# PhantomPowerSupply_Schematic.net
KiCad netlist of a schematic drawn in Altium Designer
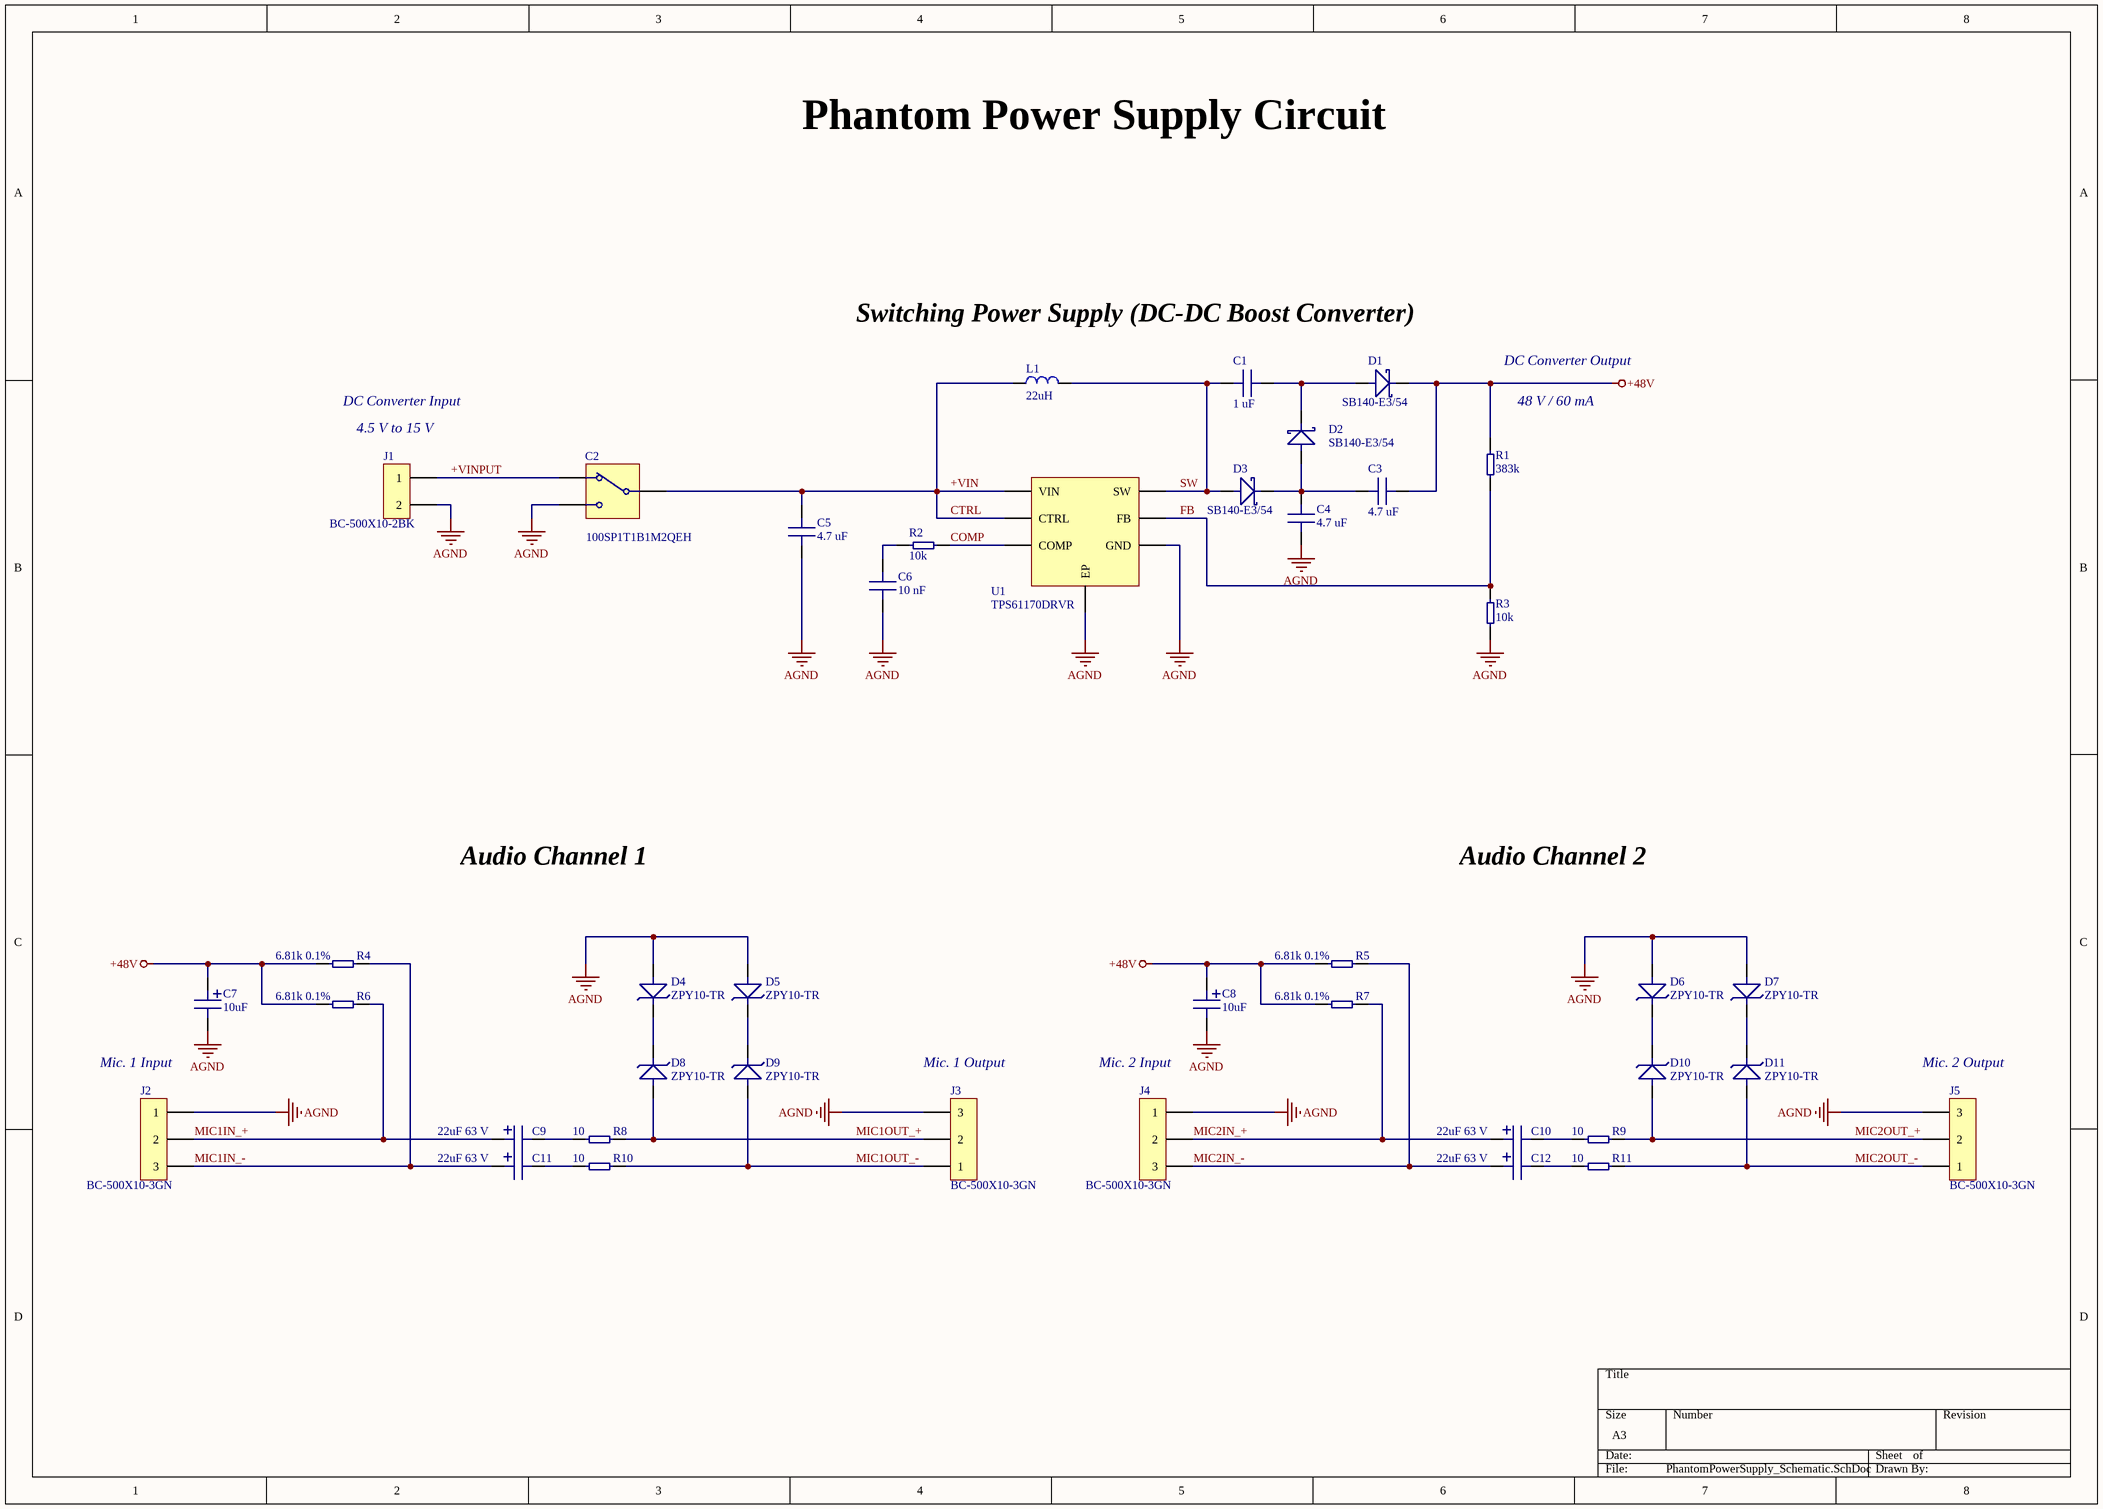
[diagram p0: PhantomPowerSupply_Schematic.SchDoc]

(export (version "E")
  (design (tool "Eeschema 10.0.6"))
  (components
    (comp (ref "C1")
      (value "1 uF")
      (footprint "CRADIAL-CERAMIC-BROWN")
      (description "Multilayer Ceramic Capacitors MLCC - Leaded 1uF 50volts 10% X7R 5mm LS")
      (fields
        (field (name "MANUFACTURER") "Vishay / BC Components")
        (field (name "MANUFACTURER PART NUMBER") "K105K20X7RF5TH5")
      )
      (libsource (lib "PhantomPowerSupply_SchematicLibrary") (part "K105K20X7RF5TH5"))
    )
    (comp (ref "C2")
      (value "100SP1T1B1M2QEH")
      (footprint "SPDT-M2")
      (description "Toggle Switches SPDT ON-ON PC MNT")
      (fields (field (name "MANUFACTURER") "E-Switch"))
      (libsource (lib "PhantomPowerSupply_SchematicLibrary") (part "100SP1T1B1M2QEH"))
    )
    (comp (ref "C3")
      (value "4.7 uF")
      (footprint "CRADIAL-CERAMIC")
      (description "Multilayer Ceramic Capacitors MLCC - Leaded 4.7uF 50volts X7R +/-10%")
      (fields (field (name "MANUFACTURER") "TDK") (field (name "MANUFACTURER PART NUMBER") "FK11X7R1H475K"))
      (libsource (lib "PhantomPowerSupply_SchematicLibrary") (part "FK11X7R1H475K"))
    )
    (comp (ref "C4")
      (value "4.7 uF")
      (footprint "CRADIAL-CERAMIC")
      (description "Multilayer Ceramic Capacitors MLCC - Leaded 4.7uF 50volts X7R +/-10%")
      (fields (field (name "MANUFACTURER") "TDK") (field (name "MANUFACTURER PART NUMBER") "FK11X7R1H475K"))
      (libsource (lib "PhantomPowerSupply_SchematicLibrary") (part "FK11X7R1H475K"))
    )
    (comp (ref "C5")
      (value "4.7 uF")
      (footprint "CRADIAL-CERAMIC")
      (description "Multilayer Ceramic Capacitors MLCC - Leaded 4.7uF 50volts X7R +/-10%")
      (fields (field (name "MANUFACTURER") "TDK") (field (name "MANUFACTURER PART NUMBER") "FK11X7R1H475K"))
      (libsource (lib "PhantomPowerSupply_SchematicLibrary") (part "FK11X7R1H475K"))
    )
    (comp (ref "C6")
      (value "10 nF")
      (footprint "CRADIAL-CERAMIC-BROWN")
      (description "Multilayer Ceramic Capacitors MLCC - Leaded .01uF 50volts 10% 5.0mm X7R")
      (fields
        (field (name "MANUFACTURER") "Vishay / BC Components")
        (field (name "MANUFACTURER PART NUMBER") "K103K15X7RF5UH5")
      )
      (libsource (lib "PhantomPowerSupply_SchematicLibrary") (part "K103K15X7RF5UH5"))
    )
    (comp (ref "C7")
      (value "10uF")
      (footprint "C-ELECTROLYTIC-RADIAL")
      (description "Aluminium Electrolytic Capacitors - Leaded 50V 10uF 20% 5x11mm")
      (fields
        (field (name "MANUFACTURER") "Lelon")
        (field (name "MANUFACTURER PART NUMBER") "REA100M1HBK-0511P")
      )
      (libsource (lib "PhantomPowerSupply_SchematicLibrary") (part "REA100M1HBK-0511P"))
    )
    (comp (ref "C8")
      (value "10uF")
      (footprint "C-ELECTROLYTIC-RADIAL")
      (description "Aluminium Electrolytic Capacitors - Leaded 50V 10uF 20% 5x11mm")
      (fields
        (field (name "MANUFACTURER") "Lelon")
        (field (name "MANUFACTURER PART NUMBER") "REA100M1HBK-0511P")
      )
      (libsource (lib "PhantomPowerSupply_SchematicLibrary") (part "REA100M1HBK-0511P"))
    )
    (comp (ref "C9")
      (value "22uF 63 V")
      (footprint "C-ELECTROLYTIC-RADIAL")
      (description "Aluminium Electrolytic Capacitors - Leaded 63V 22uF 20% 6.3x11 mm")
      (fields
        (field (name "MANUFACTURER") "Lelon")
        (field (name "MANUFACTURER PART NUMBER") "REA220M1JBK-0611P")
      )
      (libsource (lib "PhantomPowerSupply_SchematicLibrary") (part "REA220M1JBK-0611P"))
    )
    (comp (ref "C10")
      (value "22uF 63 V")
      (footprint "C-ELECTROLYTIC-RADIAL")
      (description "Aluminium Electrolytic Capacitors - Leaded 63V 22uF 20% 6.3x11 mm")
      (fields
        (field (name "MANUFACTURER") "Lelon")
        (field (name "MANUFACTURER PART NUMBER") "REA220M1JBK-0611P")
      )
      (libsource (lib "PhantomPowerSupply_SchematicLibrary") (part "REA220M1JBK-0611P"))
    )
    (comp (ref "C11")
      (value "22uF 63 V")
      (footprint "C-ELECTROLYTIC-RADIAL")
      (description "Aluminium Electrolytic Capacitors - Leaded 63V 22uF 20% 6.3x11 mm")
      (fields
        (field (name "MANUFACTURER") "Lelon")
        (field (name "MANUFACTURER PART NUMBER") "REA220M1JBK-0611P")
      )
      (libsource (lib "PhantomPowerSupply_SchematicLibrary") (part "REA220M1JBK-0611P"))
    )
    (comp (ref "C12")
      (value "22uF 63 V")
      (footprint "C-ELECTROLYTIC-RADIAL")
      (description "Aluminium Electrolytic Capacitors - Leaded 63V 22uF 20% 6.3x11 mm")
      (fields
        (field (name "MANUFACTURER") "Lelon")
        (field (name "MANUFACTURER PART NUMBER") "REA220M1JBK-0611P")
      )
      (libsource (lib "PhantomPowerSupply_SchematicLibrary") (part "REA220M1JBK-0611P"))
    )
    (comp (ref "D1")
      (value "SB140-E3/54")
      (footprint "D-SCHOTTKY-AXIAL")
      (description "Schottky Diodes & Rectifiers 40 Volt 1.0 Amp 50 Amp IFSM")
      (fields (field (name "MANUFACTURER") "Vishay Semiconductors"))
      (libsource (lib "PhantomPowerSupply_SchematicLibrary") (part "SB140-E3/54"))
    )
    (comp (ref "D2")
      (value "SB140-E3/54")
      (footprint "D-SCHOTTKY-AXIAL")
      (description "Schottky Diodes & Rectifiers 40 Volt 1.0 Amp 50 Amp IFSM")
      (fields (field (name "MANUFACTURER") "Vishay Semiconductors"))
      (libsource (lib "PhantomPowerSupply_SchematicLibrary") (part "SB140-E3/54"))
    )
    (comp (ref "D3")
      (value "SB140-E3/54")
      (footprint "D-SCHOTTKY-AXIAL")
      (description "Schottky Diodes & Rectifiers 40 Volt 1.0 Amp 50 Amp IFSM")
      (fields (field (name "MANUFACTURER") "Vishay Semiconductors"))
      (libsource (lib "PhantomPowerSupply_SchematicLibrary") (part "SB140-E3/54"))
    )
    (comp (ref "D4")
      (value "ZPY10-TR")
      (footprint "D-ZENER-AXIAL")
      (description "Zener Diodes 10 Volt 1.3 Watt 5%")
      (fields (field (name "MANUFACTURER") "Vishay Semiconductors"))
      (libsource (lib "PhantomPowerSupply_SchematicLibrary") (part "ZPY10-TR"))
    )
    (comp (ref "D5")
      (value "ZPY10-TR")
      (footprint "D-ZENER-AXIAL")
      (description "Zener Diodes 10 Volt 1.3 Watt 5%")
      (fields (field (name "MANUFACTURER") "Vishay Semiconductors"))
      (libsource (lib "PhantomPowerSupply_SchematicLibrary") (part "ZPY10-TR"))
    )
    (comp (ref "D6")
      (value "ZPY10-TR")
      (footprint "D-ZENER-AXIAL")
      (description "Zener Diodes 10 Volt 1.3 Watt 5%")
      (fields (field (name "MANUFACTURER") "Vishay Semiconductors"))
      (libsource (lib "PhantomPowerSupply_SchematicLibrary") (part "ZPY10-TR"))
    )
    (comp (ref "D7")
      (value "ZPY10-TR")
      (footprint "D-ZENER-AXIAL")
      (description "Zener Diodes 10 Volt 1.3 Watt 5%")
      (fields (field (name "MANUFACTURER") "Vishay Semiconductors"))
      (libsource (lib "PhantomPowerSupply_SchematicLibrary") (part "ZPY10-TR"))
    )
    (comp (ref "D8")
      (value "ZPY10-TR")
      (footprint "D-ZENER-AXIAL")
      (description "Zener Diodes 10 Volt 1.3 Watt 5%")
      (fields (field (name "MANUFACTURER") "Vishay Semiconductors"))
      (libsource (lib "PhantomPowerSupply_SchematicLibrary") (part "ZPY10-TR"))
    )
    (comp (ref "D9")
      (value "ZPY10-TR")
      (footprint "D-ZENER-AXIAL")
      (description "Zener Diodes 10 Volt 1.3 Watt 5%")
      (fields (field (name "MANUFACTURER") "Vishay Semiconductors"))
      (libsource (lib "PhantomPowerSupply_SchematicLibrary") (part "ZPY10-TR"))
    )
    (comp (ref "D10")
      (value "ZPY10-TR")
      (footprint "D-ZENER-AXIAL")
      (description "Zener Diodes 10 Volt 1.3 Watt 5%")
      (fields (field (name "MANUFACTURER") "Vishay Semiconductors"))
      (libsource (lib "PhantomPowerSupply_SchematicLibrary") (part "ZPY10-TR"))
    )
    (comp (ref "D11")
      (value "ZPY10-TR")
      (footprint "D-ZENER-AXIAL")
      (description "Zener Diodes 10 Volt 1.3 Watt 5%")
      (fields (field (name "MANUFACTURER") "Vishay Semiconductors"))
      (libsource (lib "PhantomPowerSupply_SchematicLibrary") (part "ZPY10-TR"))
    )
    (comp (ref "J1")
      (value "BC-500X10-2BK")
      (footprint "SCREW-CON-2POS")
      (description "Fixed Terminal Blocks BC-500X10- 2 BK")
      (fields
        (field (name "MANUFACTURER") "Phoenix Contact")
        (field (name "MANUFACTURER PART NUMBER") "5441537")
      )
      (libsource (lib "PhantomPowerSupply_SchematicLibrary") (part "5441537"))
    )
    (comp (ref "J2")
      (value "BC-500X10-3GN")
      (footprint "SCREW-CON-3POS")
      (description "Fixed Terminal Blocks BC-500X10- 3 GN 5.00 MM PITCH")
      (fields
        (field (name "MANUFACTURER") "Phoenix Contact")
        (field (name "MANUFACTURER PART NUMBER") "5442183")
      )
      (libsource (lib "") (part "5442183_1"))
    )
    (comp (ref "J3")
      (value "BC-500X10-3GN")
      (footprint "SCREW-CON-3POS")
      (description "Fixed Terminal Blocks BC-500X10- 3 GN 5.00 MM PITCH")
      (fields
        (field (name "MANUFACTURER") "Phoenix Contact")
        (field (name "MANUFACTURER PART NUMBER") "5442183")
      )
      (libsource (lib "PhantomPowerSupply_SchematicLibrary") (part "5442183"))
    )
    (comp (ref "J4")
      (value "BC-500X10-3GN")
      (footprint "SCREW-CON-3POS")
      (description "Fixed Terminal Blocks BC-500X10- 3 GN 5.00 MM PITCH")
      (fields
        (field (name "MANUFACTURER") "Phoenix Contact")
        (field (name "MANUFACTURER PART NUMBER") "5442183")
      )
      (libsource (lib "") (part "5442183_1"))
    )
    (comp (ref "J5")
      (value "BC-500X10-3GN")
      (footprint "SCREW-CON-3POS")
      (description "Fixed Terminal Blocks BC-500X10- 3 GN 5.00 MM PITCH")
      (fields
        (field (name "MANUFACTURER") "Phoenix Contact")
        (field (name "MANUFACTURER PART NUMBER") "5442183")
      )
      (libsource (lib "PhantomPowerSupply_SchematicLibrary") (part "5442183"))
    )
    (comp (ref "L1")
      (value "22uH")
      (footprint "L-AXIAL")
      (description "Fixed Inductors 22uH 5%")
      (fields
        (field (name "MANUFACTURER") "J.W. Miller")
        (field (name "MANUFACTURER PART NUMBER") "78F220J-RC")
      )
      (libsource (lib "PhantomPowerSupply_SchematicLibrary") (part "78F220J-RC"))
    )
    (comp (ref "R1")
      (value "383k")
      (footprint "R-AXIAL")
      (description "Metal Film Resistors - Through Hole 1/4 WATT 383K OHM 1%")
      (fields
        (field (name "MANUFACTURER") "KOA Speer")
        (field (name "MANUFACTURER PART NUMBER") "MF1/4DCT26A3833F")
      )
      (libsource (lib "PhantomPowerSupply_SchematicLibrary") (part "MF1/4DCT26A3833F"))
    )
    (comp (ref "R2")
      (value "10k")
      (footprint "R-AXIAL")
      (description "Metal Film Resistors - Through Hole 1/4 WATT 10K OHM 1%")
      (fields
        (field (name "MANUFACTURER") "KOA Speer")
        (field (name "MANUFACTURER PART NUMBER") "MF1/4DCT52A1002F")
      )
      (libsource (lib "PhantomPowerSupply_SchematicLibrary") (part "MF1/4DCT52A1002F"))
    )
    (comp (ref "R3")
      (value "10k")
      (footprint "R-AXIAL")
      (description "Metal Film Resistors - Through Hole 1/4 WATT 10K OHM 1%")
      (fields
        (field (name "MANUFACTURER") "KOA Speer")
        (field (name "MANUFACTURER PART NUMBER") "MF1/4DCT52A1002F")
      )
      (libsource (lib "PhantomPowerSupply_SchematicLibrary") (part "MF1/4DCT52A1002F"))
    )
    (comp (ref "R4")
      (value "6.81k 0.1%")
      (footprint "R-AXIAL")
      (description "Metal Film Resistors - Through Hole 1/10watt 6.81Kohms .1% 25ppm")
      (fields
        (field (name "MANUFACTURER") "Vishay / Dale")
        (field (name "MANUFACTURER PART NUMBER") "RN55E6811BRE6")
      )
      (libsource (lib "PhantomPowerSupply_SchematicLibrary") (part "RN55E6811BRE6"))
    )
    (comp (ref "R5")
      (value "6.81k 0.1%")
      (footprint "R-AXIAL")
      (description "Metal Film Resistors - Through Hole 1/10watt 6.81Kohms .1% 25ppm")
      (fields
        (field (name "MANUFACTURER") "Vishay / Dale")
        (field (name "MANUFACTURER PART NUMBER") "RN55E6811BRE6")
      )
      (libsource (lib "PhantomPowerSupply_SchematicLibrary") (part "RN55E6811BRE6"))
    )
    (comp (ref "R6")
      (value "6.81k 0.1%")
      (footprint "R-AXIAL")
      (description "Metal Film Resistors - Through Hole 1/10watt 6.81Kohms .1% 25ppm")
      (fields
        (field (name "MANUFACTURER") "Vishay / Dale")
        (field (name "MANUFACTURER PART NUMBER") "RN55E6811BRE6")
      )
      (libsource (lib "PhantomPowerSupply_SchematicLibrary") (part "RN55E6811BRE6"))
    )
    (comp (ref "R7")
      (value "6.81k 0.1%")
      (footprint "R-AXIAL")
      (description "Metal Film Resistors - Through Hole 1/10watt 6.81Kohms .1% 25ppm")
      (fields
        (field (name "MANUFACTURER") "Vishay / Dale")
        (field (name "MANUFACTURER PART NUMBER") "RN55E6811BRE6")
      )
      (libsource (lib "PhantomPowerSupply_SchematicLibrary") (part "RN55E6811BRE6"))
    )
    (comp (ref "R8")
      (value "10")
      (footprint "R-AXIAL")
      (description "Metal Film Resistors - Through Hole 10 OHM 1/2W 5%")
      (fields
        (field (name "MANUFACTURER") "Yageo")
        (field (name "MANUFACTURER PART NUMBER") "FRM-50JT-52-10R")
      )
      (libsource (lib "PhantomPowerSupply_SchematicLibrary") (part "FRM-50JT-52-10R"))
    )
    (comp (ref "R9")
      (value "10")
      (footprint "R-AXIAL")
      (description "Metal Film Resistors - Through Hole 10 OHM 1/2W 5%")
      (fields
        (field (name "MANUFACTURER") "Yageo")
        (field (name "MANUFACTURER PART NUMBER") "FRM-50JT-52-10R")
      )
      (libsource (lib "PhantomPowerSupply_SchematicLibrary") (part "FRM-50JT-52-10R"))
    )
    (comp (ref "R10")
      (value "10")
      (footprint "R-AXIAL")
      (description "Metal Film Resistors - Through Hole 10 OHM 1/2W 5%")
      (fields
        (field (name "MANUFACTURER") "Yageo")
        (field (name "MANUFACTURER PART NUMBER") "FRM-50JT-52-10R")
      )
      (libsource (lib "PhantomPowerSupply_SchematicLibrary") (part "FRM-50JT-52-10R"))
    )
    (comp (ref "R11")
      (value "10")
      (footprint "R-AXIAL")
      (description "Metal Film Resistors - Through Hole 10 OHM 1/2W 5%")
      (fields
        (field (name "MANUFACTURER") "Yageo")
        (field (name "MANUFACTURER PART NUMBER") "FRM-50JT-52-10R")
      )
      (libsource (lib "PhantomPowerSupply_SchematicLibrary") (part "FRM-50JT-52-10R"))
    )
    (comp (ref "U1")
      (value "TPS61170DRVR")
      (footprint "S-PWSON-N6")
      (description "Voltage Regulators - Switching Regulators 1.2A Sw Hi Vltg Boost Conv")
      (fields (field (name "MANUFACTURER") "Texas Instruments"))
      (libsource (lib "PhantomPowerSupply_SchematicLibrary") (part "TPS61170DRVR"))
    )
  )
  (nets
    (net (code "1") (name "+48V") (class "Default")
      (node (ref "C3") (pin "2") (pinfunction "2_2") (pintype "passive"))
      (node (ref "C7") (pin "1") (pinfunction "1_1") (pintype "passive"))
      (node (ref "C8") (pin "1") (pinfunction "1_1") (pintype "passive"))
      (node (ref "D1") (pin "2") (pinfunction "2_2") (pintype "passive"))
      (node (ref "R1") (pin "2") (pinfunction "2_2") (pintype "passive"))
      (node (ref "R4") (pin "1") (pinfunction "1_1") (pintype "passive"))
      (node (ref "R5") (pin "1") (pinfunction "1_1") (pintype "passive"))
      (node (ref "R6") (pin "1") (pinfunction "1_1") (pintype "passive"))
      (node (ref "R7") (pin "1") (pinfunction "1_1") (pintype "passive"))
    )
    (net (code "2") (name "/+VIN") (class "Default")
      (node (ref "C2") (pin "2") (pinfunction "2_2") (pintype "passive"))
      (node (ref "C5") (pin "2") (pinfunction "2_2") (pintype "passive"))
      (node (ref "L1") (pin "1") (pinfunction "1_1") (pintype "passive"))
      (node (ref "U1") (pin "5") (pinfunction "CTRL_5") (pintype "passive"))
      (node (ref "U1") (pin "6") (pinfunction "VIN_6") (pintype "passive"))
    )
    (net (code "3") (name "/+VINPUT") (class "Default")
      (node (ref "C2") (pin "1") (pinfunction "1_1") (pintype "passive"))
      (node (ref "J1") (pin "1") (pinfunction "1_1") (pintype "passive"))
    )
    (net (code "4") (name "/COMP") (class "Default")
      (node (ref "R2") (pin "2") (pinfunction "2_2") (pintype "passive"))
      (node (ref "U1") (pin "2") (pinfunction "COMP_2") (pintype "passive"))
    )
    (net (code "5") (name "/FB") (class "Default")
      (node (ref "R1") (pin "1") (pinfunction "1_1") (pintype "passive"))
      (node (ref "R3") (pin "2") (pinfunction "2_2") (pintype "passive"))
      (node (ref "U1") (pin "1") (pinfunction "FB_1") (pintype "passive"))
    )
    (net (code "6") (name "/MIC1IN_+") (class "Default")
      (node (ref "C9") (pin "1") (pinfunction "1_1") (pintype "passive"))
      (node (ref "J2") (pin "2") (pinfunction "2_2") (pintype "passive"))
      (node (ref "R6") (pin "2") (pinfunction "2_2") (pintype "passive"))
    )
    (net (code "7") (name "/MIC1IN_-") (class "Default")
      (node (ref "C11") (pin "1") (pinfunction "1_1") (pintype "passive"))
      (node (ref "J2") (pin "3") (pinfunction "3_3") (pintype "passive"))
      (node (ref "R4") (pin "2") (pinfunction "2_2") (pintype "passive"))
    )
    (net (code "8") (name "/MIC1OUT_+") (class "Default")
      (node (ref "D8") (pin "1") (pinfunction "1_1") (pintype "passive"))
      (node (ref "J3") (pin "2") (pinfunction "2_2") (pintype "passive"))
      (node (ref "R8") (pin "2") (pinfunction "2_2") (pintype "passive"))
    )
    (net (code "9") (name "/MIC1OUT_-") (class "Default")
      (node (ref "D9") (pin "1") (pinfunction "1_1") (pintype "passive"))
      (node (ref "J3") (pin "1") (pinfunction "1_1") (pintype "passive"))
      (node (ref "R10") (pin "2") (pinfunction "2_2") (pintype "passive"))
    )
    (net (code "10") (name "/MIC2IN_+") (class "Default")
      (node (ref "C10") (pin "1") (pinfunction "1_1") (pintype "passive"))
      (node (ref "J4") (pin "2") (pinfunction "2_2") (pintype "passive"))
      (node (ref "R7") (pin "2") (pinfunction "2_2") (pintype "passive"))
    )
    (net (code "11") (name "/MIC2IN_-") (class "Default")
      (node (ref "C12") (pin "1") (pinfunction "1_1") (pintype "passive"))
      (node (ref "J4") (pin "3") (pinfunction "3_3") (pintype "passive"))
      (node (ref "R5") (pin "2") (pinfunction "2_2") (pintype "passive"))
    )
    (net (code "12") (name "/MIC2OUT_+") (class "Default")
      (node (ref "D10") (pin "1") (pinfunction "1_1") (pintype "passive"))
      (node (ref "J5") (pin "2") (pinfunction "2_2") (pintype "passive"))
      (node (ref "R9") (pin "2") (pinfunction "2_2") (pintype "passive"))
    )
    (net (code "13") (name "/MIC2OUT_-") (class "Default")
      (node (ref "D11") (pin "1") (pinfunction "1_1") (pintype "passive"))
      (node (ref "J5") (pin "1") (pinfunction "1_1") (pintype "passive"))
      (node (ref "R11") (pin "2") (pinfunction "2_2") (pintype "passive"))
    )
    (net (code "14") (name "/SW") (class "Default")
      (node (ref "C1") (pin "1") (pinfunction "1_1") (pintype "passive"))
      (node (ref "D3") (pin "1") (pinfunction "1_1") (pintype "passive"))
      (node (ref "L1") (pin "2") (pinfunction "2_2") (pintype "passive"))
      (node (ref "U1") (pin "4") (pinfunction "SW_4") (pintype "passive"))
    )
    (net (code "15") (name "AGND") (class "Default")
      (node (ref "C2") (pin "3") (pinfunction "3_3") (pintype "passive"))
      (node (ref "C4") (pin "1") (pinfunction "1_1") (pintype "passive"))
      (node (ref "C5") (pin "1") (pinfunction "1_1") (pintype "passive"))
      (node (ref "C6") (pin "1") (pinfunction "1_1") (pintype "passive"))
      (node (ref "C7") (pin "2") (pinfunction "2_2") (pintype "passive"))
      (node (ref "C8") (pin "2") (pinfunction "2_2") (pintype "passive"))
      (node (ref "D4") (pin "1") (pinfunction "1_1") (pintype "passive"))
      (node (ref "D5") (pin "1") (pinfunction "1_1") (pintype "passive"))
      (node (ref "D6") (pin "1") (pinfunction "1_1") (pintype "passive"))
      (node (ref "D7") (pin "1") (pinfunction "1_1") (pintype "passive"))
      (node (ref "J1") (pin "2") (pinfunction "2_2") (pintype "passive"))
      (node (ref "J2") (pin "1") (pinfunction "1_1") (pintype "passive"))
      (node (ref "J3") (pin "3") (pinfunction "3_3") (pintype "passive"))
      (node (ref "J4") (pin "1") (pinfunction "1_1") (pintype "passive"))
      (node (ref "J5") (pin "3") (pinfunction "3_3") (pintype "passive"))
      (node (ref "R3") (pin "1") (pinfunction "1_1") (pintype "passive"))
      (node (ref "U1") (pin "3") (pinfunction "GND_3") (pintype "passive"))
      (node (ref "U1") (pin "7") (pinfunction "EP_7") (pintype "passive"))
    )
    (net (code "16") (name "Net-(C1-Pad2)") (class "Default")
      (node (ref "C1") (pin "2") (pinfunction "2_2") (pintype "passive"))
      (node (ref "D1") (pin "1") (pinfunction "1_1") (pintype "passive"))
      (node (ref "D2") (pin "2") (pinfunction "2_2") (pintype "passive"))
    )
    (net (code "17") (name "Net-(C3-Pad1)") (class "Default")
      (node (ref "C3") (pin "1") (pinfunction "1_1") (pintype "passive"))
      (node (ref "C4") (pin "2") (pinfunction "2_2") (pintype "passive"))
      (node (ref "D2") (pin "1") (pinfunction "1_1") (pintype "passive"))
      (node (ref "D3") (pin "2") (pinfunction "2_2") (pintype "passive"))
    )
    (net (code "18") (name "Net-(C6-Pad2)") (class "Default")
      (node (ref "C6") (pin "2") (pinfunction "2_2") (pintype "passive"))
      (node (ref "R2") (pin "1") (pinfunction "1_1") (pintype "passive"))
    )
    (net (code "19") (name "Net-(C9-Pad2)") (class "Default")
      (node (ref "C9") (pin "2") (pinfunction "2_2") (pintype "passive"))
      (node (ref "R8") (pin "1") (pinfunction "1_1") (pintype "passive"))
    )
    (net (code "20") (name "Net-(C10-Pad2)") (class "Default")
      (node (ref "C10") (pin "2") (pinfunction "2_2") (pintype "passive"))
      (node (ref "R9") (pin "1") (pinfunction "1_1") (pintype "passive"))
    )
    (net (code "21") (name "Net-(C11-Pad2)") (class "Default")
      (node (ref "C11") (pin "2") (pinfunction "2_2") (pintype "passive"))
      (node (ref "R10") (pin "1") (pinfunction "1_1") (pintype "passive"))
    )
    (net (code "22") (name "Net-(C12-Pad2)") (class "Default")
      (node (ref "C12") (pin "2") (pinfunction "2_2") (pintype "passive"))
      (node (ref "R11") (pin "1") (pinfunction "1_1") (pintype "passive"))
    )
    (net (code "23") (name "Net-(D4-Pad2)") (class "Default")
      (node (ref "D4") (pin "2") (pinfunction "2_2") (pintype "passive"))
      (node (ref "D8") (pin "2") (pinfunction "2_2") (pintype "passive"))
    )
    (net (code "24") (name "Net-(D5-Pad2)") (class "Default")
      (node (ref "D5") (pin "2") (pinfunction "2_2") (pintype "passive"))
      (node (ref "D9") (pin "2") (pinfunction "2_2") (pintype "passive"))
    )
    (net (code "25") (name "Net-(D10-Pad2)") (class "Default")
      (node (ref "D10") (pin "2") (pinfunction "2_2") (pintype "passive"))
      (node (ref "D6") (pin "2") (pinfunction "2_2") (pintype "passive"))
    )
    (net (code "26") (name "Net-(D11-Pad2)") (class "Default")
      (node (ref "D11") (pin "2") (pinfunction "2_2") (pintype "passive"))
      (node (ref "D7") (pin "2") (pinfunction "2_2") (pintype "passive"))
    )
  )
)
